# LEDS_-_Status.net
KiCad netlist of a schematic drawn in Altium Designer
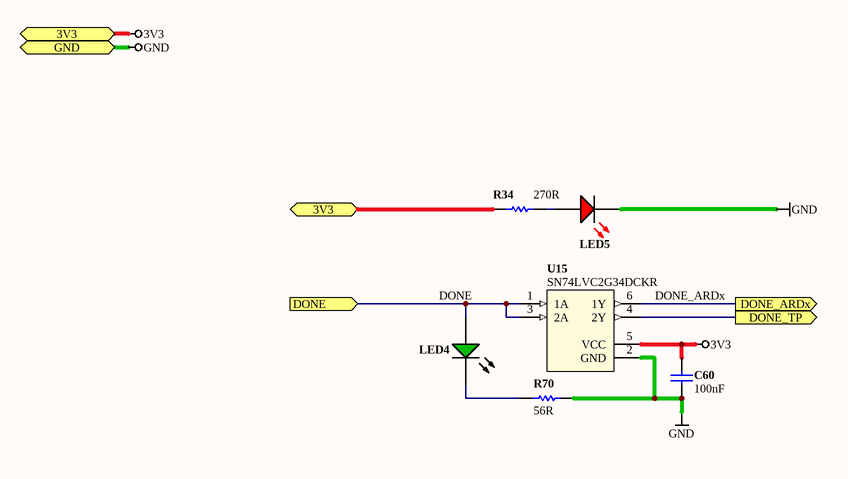
[diagram p0: LEDS - Status.SchDoc]

(export (version "E")
  (design (tool "Eeschema 10.0.6"))
  (components
    (comp (ref "C60")
      (value "100nF")
      (footprint "CAPC0402(1005)60_L")
      (description "CAP 100nF 10V ±5% 0402 (1005 Metric) Thickness 0.6mm SMD")
      (fields (field (name "TOLERANCE") "±5%") (field (name "MANUFACTURER PART NUMBER") "C0402C104K8PACTU"))
      (libsource (lib "Altium Content Vault") (part "CMP-1034-02064-1"))
    )
    (comp (ref "LED4")
      (value "LED_GREEN_APT1608SGC")
      (footprint "LED0603")
      (description "SMD 0603 LED, GREEN")
      (fields (field (name "PARTNUMBER") "APT1608SGC"))
      (libsource (lib "LED-GREEN-APT1608SGC") (part "LED_GREEN_APT1608SGC"))
    )
    (comp (ref "LED5")
      (value "0402-LED-RED")
      (footprint "LED_0402")
      (description "0402 LED,RED")
      (fields (field (name "MANUFACTURER PART NUMBER") "LTST-C190KRKT"))
      (libsource (lib "Component_DB") (part "LED_RED_A1K2-2"))
    )
    (comp (ref "R34")
      (value "270R")
      (footprint "RESC0402(1005)40_L")
      (description "0402 (1005 Metric) 1/16 W 270R 1 Thick Film Chip Resistor")
      (fields (field (name "POWER") "1/16 W") (field (name "MANUFACTURER PART NUMBER") "RC1005F271CS"))
      (libsource (lib "Component_DB") (part "RES"))
    )
    (comp (ref "R70")
      (value "56R")
      (footprint "RESC0402(1005)_L")
      (description "56R 0.063W 1% 0402 (1005 Metric)  SMD")
      (fields (field (name "POWER") "0.063 W") (field (name "TOLERANCE") "1 %"))
      (libsource (lib "Altium Content Vault") (part "CMP-1011-00369-1"))
    )
    (comp (ref "U15")
      (value "SN74LVC2G34DCKR")
      (footprint "TI-DCK6_L")
      (description "IC BUFFER DUAL NON-INV SC706")
      (fields (field (name "MANUFACTURER") "Texas Instruments"))
      (libsource (lib "Component_Database") (part "SN74LVC2G34"))
    )
  )
  (nets
    (net (code "1") (name "/DONE") (class "Default")
      (node (ref "LED4") (pin "1") (pinfunction "A_1") (pintype "passive"))
      (node (ref "U15") (pin "1") (pinfunction "1A_1") (pintype "input"))
      (node (ref "U15") (pin "3") (pinfunction "2A_3") (pintype "input"))
    )
    (net (code "2") (name "/DONE_ARDx") (class "Default")
      (node (ref "U15") (pin "6") (pinfunction "1Y_6") (pintype "output"))
    )
    (net (code "3") (name "/DONE_TP") (class "Default")
      (node (ref "U15") (pin "4") (pinfunction "2Y_4") (pintype "output"))
    )
    (net (code "4") (name "3V3") (class "Default")
      (node (ref "C60") (pin "2") (pinfunction "2_2") (pintype "passive"))
      (node (ref "R34") (pin "1") (pinfunction "1_1") (pintype "passive"))
      (node (ref "U15") (pin "5") (pinfunction "VCC_5") (pintype "power_in"))
    )
    (net (code "5") (name "GND") (class "Default")
      (node (ref "C60") (pin "1") (pinfunction "1_1") (pintype "passive"))
      (node (ref "LED5") (pin "2") (pinfunction "K_2") (pintype "passive"))
      (node (ref "R70") (pin "2") (pinfunction "2_2") (pintype "passive"))
      (node (ref "U15") (pin "2") (pinfunction "GND_2") (pintype "power_in"))
    )
    (net (code "6") (name "Net-(LED4-K)") (class "Default")
      (node (ref "LED4") (pin "2") (pinfunction "K_2") (pintype "passive"))
      (node (ref "R70") (pin "1") (pinfunction "1_1") (pintype "passive"))
    )
    (net (code "7") (name "Net-(LED5-A)") (class "Default")
      (node (ref "LED5") (pin "1") (pinfunction "A_1") (pintype "passive"))
      (node (ref "R34") (pin "2") (pinfunction "2_2") (pintype "passive"))
    )
  )
)
